# FLASH.net
KiCad netlist of a schematic drawn in Altium Designer
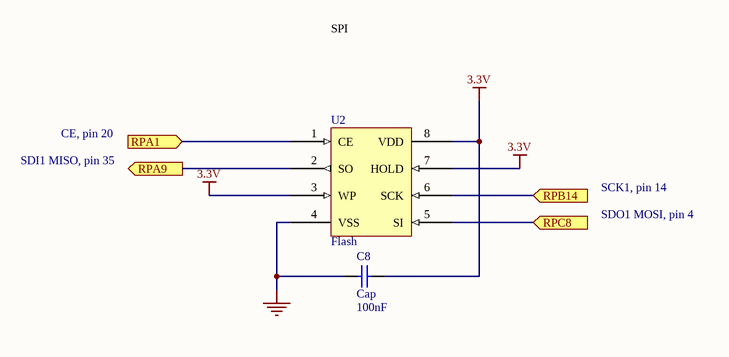
[diagram p0: FLASH.SchDoc]

(export (version "E")
  (design (tool "Eeschema 10.0.6"))
  (components
    (comp (ref "C8")
      (value "Cap")
      (footprint "0603")
      (description "Capacitor")
      (fields (field (name "ALTIUM_VALUE") "100nF") (field (name "PUBLISHER") "Altium Limited"))
      (libsource (lib "Miscellaneous Devices") (part "Cap"))
    )
    (comp (ref "U2") (value "Flash") (footprint "flash") (libsource (lib "Schlib1") (part "Flash")))
  )
  (nets
    (net (code "1") (name "/RPA1") (class "Default")
      (node (ref "U2") (pin "1") (pinfunction "CE_1") (pintype "input"))
    )
    (net (code "2") (name "/RPA9") (class "Default")
      (node (ref "U2") (pin "2") (pinfunction "SO_2") (pintype "output"))
    )
    (net (code "3") (name "/RPB14") (class "Default")
      (node (ref "U2") (pin "6") (pinfunction "SCK_6") (pintype "input"))
    )
    (net (code "4") (name "/RPC8") (class "Default")
      (node (ref "U2") (pin "5") (pinfunction "SI_5") (pintype "input"))
    )
    (net (code "5") (name "3.3V") (class "Default")
      (node (ref "C8") (pin "2") (pinfunction "2_2") (pintype "passive"))
      (node (ref "U2") (pin "3") (pinfunction "WP_3") (pintype "input"))
      (node (ref "U2") (pin "7") (pinfunction "HOLD_7") (pintype "input"))
      (node (ref "U2") (pin "8") (pinfunction "VDD_8") (pintype "power_in"))
    )
    (net (code "6") (name "GND") (class "Default")
      (node (ref "C8") (pin "1") (pinfunction "1_1") (pintype "passive"))
      (node (ref "U2") (pin "4") (pinfunction "VSS_4") (pintype "power_in"))
    )
  )
)
